# P-MT3620RDB-1-7_PIO.net
KiCad netlist of a schematic drawn in Altium Designer
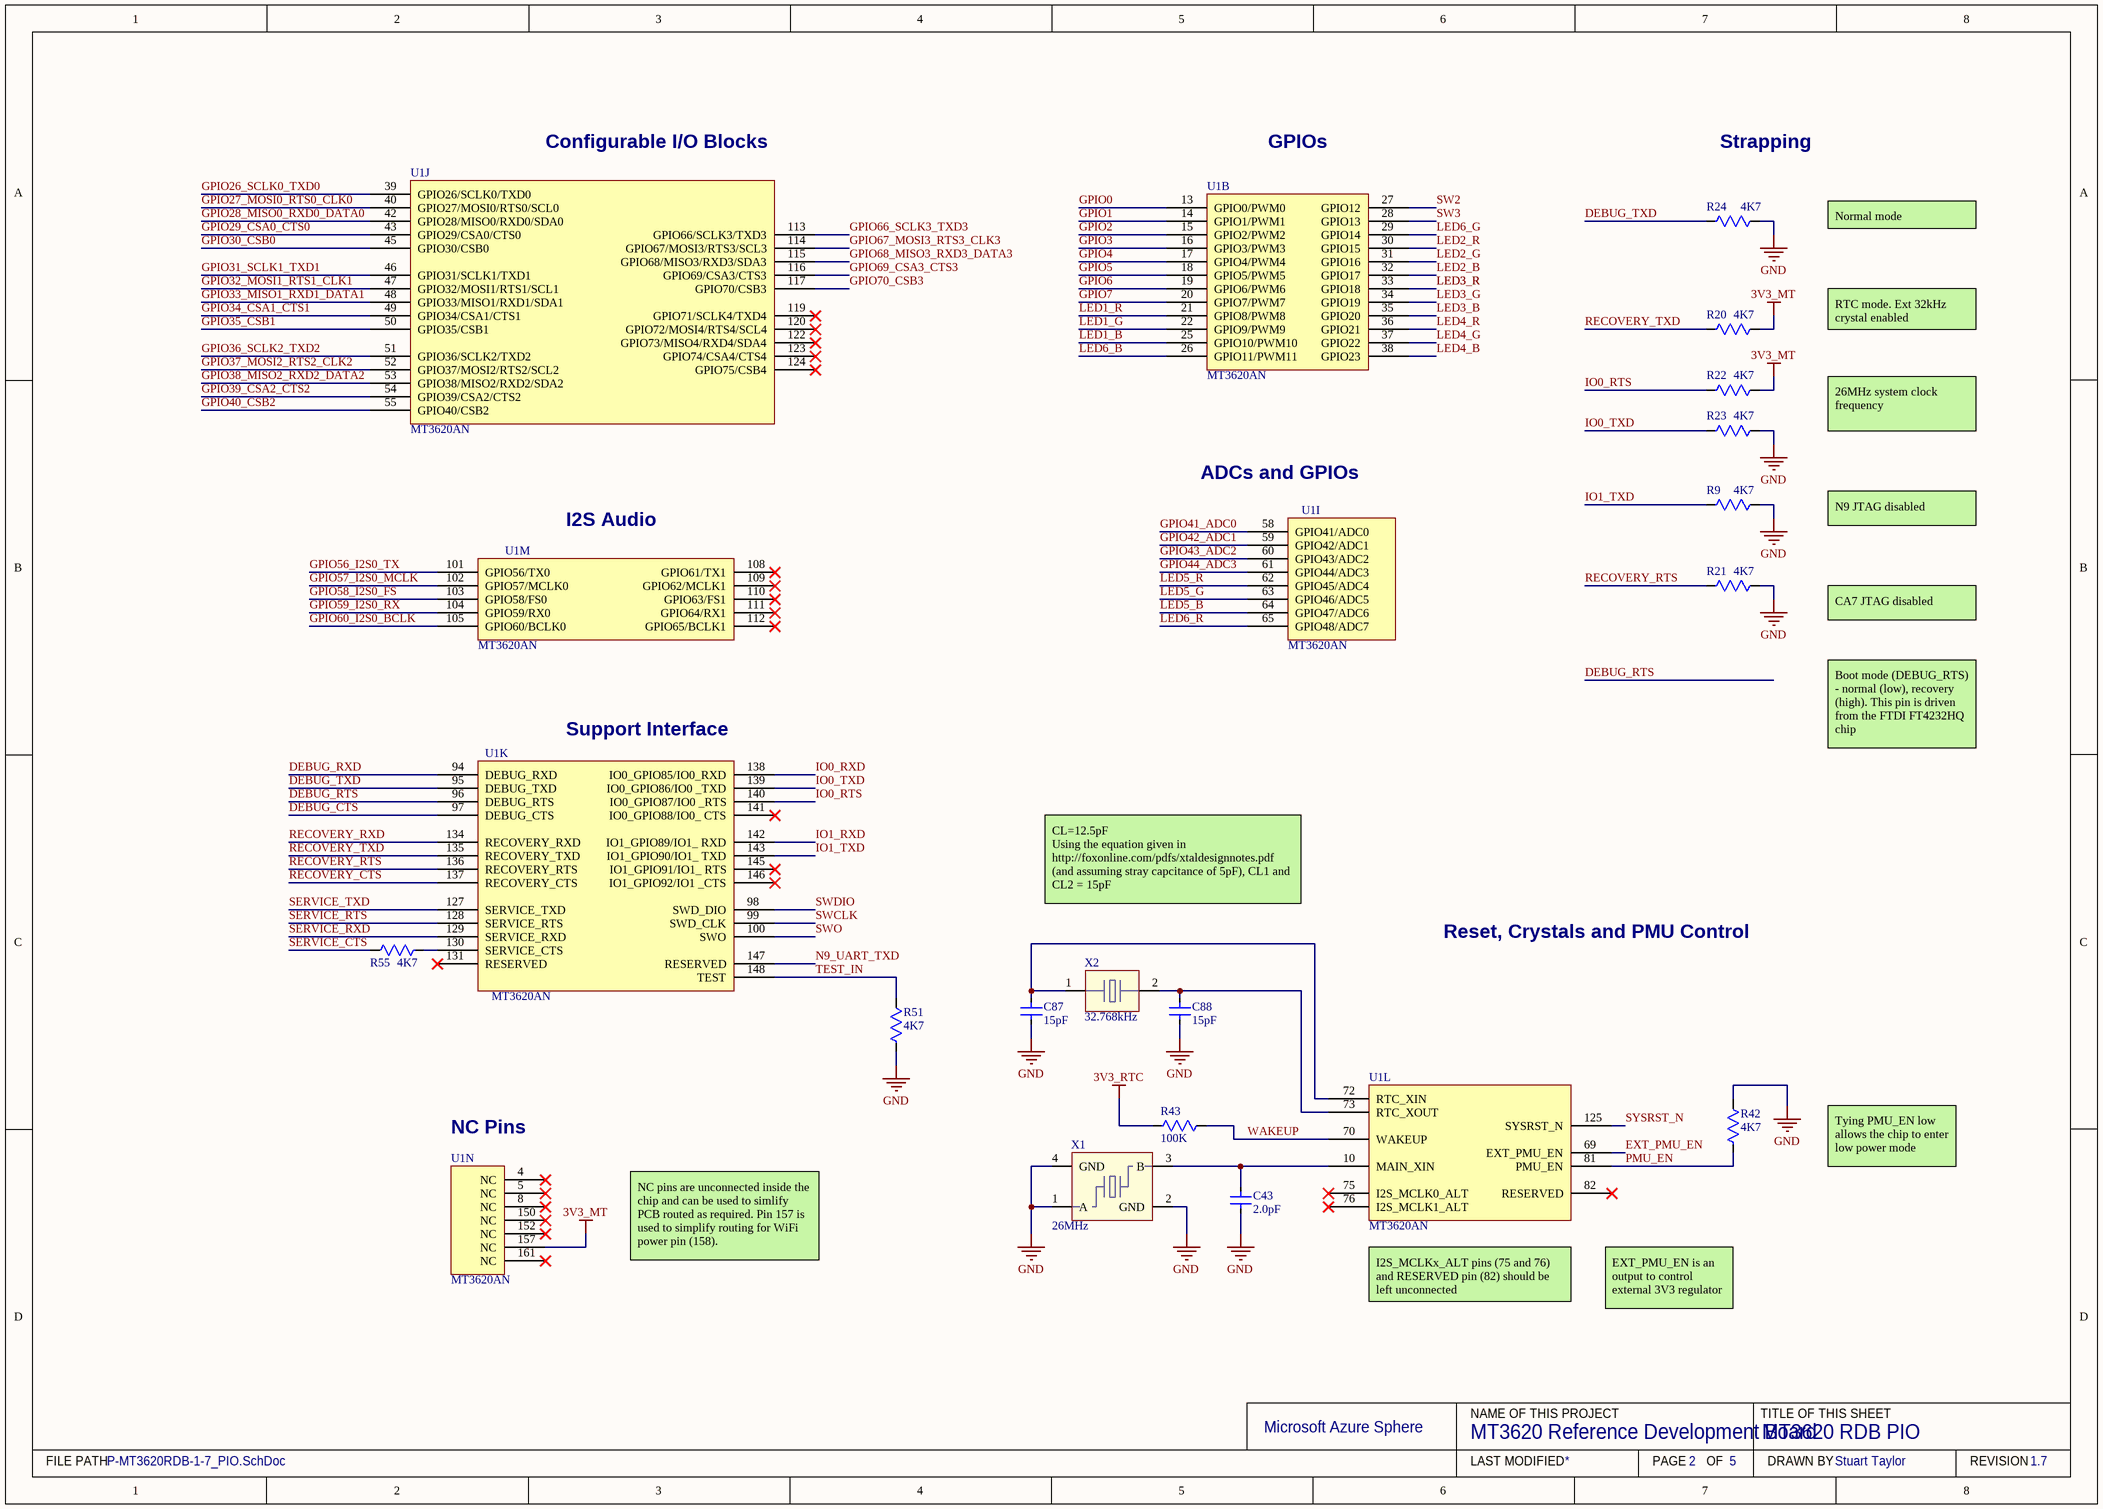
[diagram p0: P-MT3620RDB-1-7_PIO.SchDoc]

(export (version "E")
  (design (tool "Eeschema 10.0.6"))
  (components
    (comp (ref "C43")
      (value "2.0pF")
      (footprint "CAPC1005-EIA0402 0.55MM MED")
      (description "CAP CER 2PF 50V NP0 0402")
      (fields
        (field (name "MANUFACTURER") "TDK Corporation")
        (field (name "MANUFACTURER PART NUMBER") "C1005C0G1H020C050BA")
        (field (name "CAPACITANCE") "2.0pF")
      )
      (libsource (lib "TDK_Capacitor_C_0402") (part "2.0pF 0402 C0G, NP0 50V"))
    )
    (comp (ref "C87")
      (value "15pF")
      (footprint "CAPC1005-EIA0402 0.55MM MED")
      (description "CAP CER 15PF 50V 5% NP0 0402")
      (fields
        (field (name "MANUFACTURER") "TDK Corporation")
        (field (name "MANUFACTURER PART NUMBER") "C1005C0G1H150J050BA")
        (field (name "CAPACITANCE") "15pF")
      )
      (libsource (lib "TDK_Capacitor_C_0402") (part "15pF 0402 C0G, NP0 50V"))
    )
    (comp (ref "C88")
      (value "15pF")
      (footprint "CAPC1005-EIA0402 0.55MM MED")
      (description "CAP CER 15PF 50V 5% NP0 0402")
      (fields
        (field (name "MANUFACTURER") "TDK Corporation")
        (field (name "MANUFACTURER PART NUMBER") "C1005C0G1H150J050BA")
        (field (name "CAPACITANCE") "15pF")
      )
      (libsource (lib "TDK_Capacitor_C_0402") (part "15pF 0402 C0G, NP0 50V"))
    )
    (comp (ref "R9")
      (value "4K7")
      (footprint "RES 0402 MEDIUM DENSITY")
      (description "RES 4.7K OHM 1/10W 1% 0402 SMD")
      (fields
        (field (name "MANUFACTURER") "Panasonic Electronic Components")
        (field (name "MANUFACTURER PART NUMBER") "ERJ-2RKF4701X")
        (field (name "RESISTANCE (OHMS)") "4K7")
      )
      (libsource (lib "Panasonic_Resistor_ERJ2R") (part "4.7K"))
    )
    (comp (ref "R20")
      (value "4K7")
      (footprint "RES 0402 MEDIUM DENSITY")
      (description "RES 4.7K OHM 1/10W 1% 0402 SMD")
      (fields
        (field (name "MANUFACTURER") "Panasonic Electronic Components")
        (field (name "MANUFACTURER PART NUMBER") "ERJ-2RKF4701X")
        (field (name "RESISTANCE (OHMS)") "4K7")
      )
      (libsource (lib "Panasonic_Resistor_ERJ2R") (part "4.7K"))
    )
    (comp (ref "R21")
      (value "4K7")
      (footprint "RES 0402 MEDIUM DENSITY")
      (description "RES 4.7K OHM 1/10W 1% 0402 SMD")
      (fields
        (field (name "MANUFACTURER") "Panasonic Electronic Components")
        (field (name "MANUFACTURER PART NUMBER") "ERJ-2RKF4701X")
        (field (name "RESISTANCE (OHMS)") "4K7")
      )
      (libsource (lib "Panasonic_Resistor_ERJ2R") (part "4.7K"))
    )
    (comp (ref "R22")
      (value "4K7")
      (footprint "RES 0402 MEDIUM DENSITY")
      (description "RES 4.7K OHM 1/10W 1% 0402 SMD")
      (fields
        (field (name "MANUFACTURER") "Panasonic Electronic Components")
        (field (name "MANUFACTURER PART NUMBER") "ERJ-2RKF4701X")
        (field (name "RESISTANCE (OHMS)") "4K7")
      )
      (libsource (lib "Panasonic_Resistor_ERJ2R") (part "4.7K"))
    )
    (comp (ref "R23")
      (value "4K7")
      (footprint "RES 0402 MEDIUM DENSITY")
      (description "RES 4.7K OHM 1/10W 1% 0402 SMD")
      (fields
        (field (name "MANUFACTURER") "Panasonic Electronic Components")
        (field (name "MANUFACTURER PART NUMBER") "ERJ-2RKF4701X")
        (field (name "RESISTANCE (OHMS)") "4K7")
      )
      (libsource (lib "Panasonic_Resistor_ERJ2R") (part "4.7K"))
    )
    (comp (ref "R24")
      (value "4K7")
      (footprint "RES 0402 MEDIUM DENSITY")
      (description "RES 4.7K OHM 1/10W 1% 0402 SMD")
      (fields
        (field (name "MANUFACTURER") "Panasonic Electronic Components")
        (field (name "MANUFACTURER PART NUMBER") "ERJ-2RKF4701X")
        (field (name "RESISTANCE (OHMS)") "4K7")
      )
      (libsource (lib "Panasonic_Resistor_ERJ2R") (part "4.7K"))
    )
    (comp (ref "R42")
      (value "4K7")
      (footprint "RES 0402 MEDIUM DENSITY")
      (description "RES 4.7K OHM 1/10W 1% 0402 SMD")
      (fields
        (field (name "MANUFACTURER") "Panasonic Electronic Components")
        (field (name "MANUFACTURER PART NUMBER") "ERJ-2RKF4701X")
        (field (name "RESISTANCE (OHMS)") "4K7")
      )
      (libsource (lib "Panasonic_Resistor_ERJ2R") (part "4.7K"))
    )
    (comp (ref "R43")
      (value "100K")
      (footprint "RES 0402 MEDIUM DENSITY")
      (description "RES 100K OHM 1/10W 1% 0402 SMD")
      (fields
        (field (name "MANUFACTURER") "Panasonic Electronic Components")
        (field (name "MANUFACTURER PART NUMBER") "ERJ-2RKF1003X")
        (field (name "RESISTANCE (OHMS)") "100K")
      )
      (libsource (lib "Panasonic_Resistor_ERJ2R") (part "100K"))
    )
    (comp (ref "R51")
      (value "4K7")
      (footprint "RES 0402 MEDIUM DENSITY")
      (description "RES 4.7K OHM 1/10W 1% 0402 SMD")
      (fields
        (field (name "MANUFACTURER") "Panasonic Electronic Components")
        (field (name "MANUFACTURER PART NUMBER") "ERJ-2RKF4701X")
        (field (name "RESISTANCE (OHMS)") "4K7")
      )
      (libsource (lib "Panasonic_Resistor_ERJ2R") (part "4.7K"))
    )
    (comp (ref "R55")
      (value "4K7")
      (footprint "RES 0402 MEDIUM DENSITY")
      (description "RES 4.7K OHM 1/10W 1% 0402 SMD")
      (fields
        (field (name "MANUFACTURER") "Panasonic Electronic Components")
        (field (name "MANUFACTURER PART NUMBER") "ERJ-2RKF4701X")
        (field (name "RESISTANCE (OHMS)") "4K7")
      )
      (libsource (lib "Panasonic_Resistor_ERJ2R") (part "4.7K"))
    )
    (comp (ref "U1")
      (value "MT3620AN")
      (footprint "MT3620_MaskSquaresVias50")
      (fields (field (name "MANUFACTURER") "MediaTek Inc."))
      (libsource (lib "Microsoft") (part "MT3620AN"))
    )
    (comp (ref "X1")
      (value "26MHz")
      (footprint "CT2520DB26000C0FZZA1")
      (description "26MHz crystal")
      (fields
        (field (name "MANUFACTURER") "Siward")
        (field (name "MANUFACTURER PART NUMBER") "XTL581100-M118-0804")
      )
      (libsource (lib "Siward") (part "XTL581100-M118-0804"))
    )
    (comp (ref "X2")
      (value "32.768kHz")
      (footprint "9HT10-32.768KDZF-T")
      (description "32.768kHz ±20ppm Crystal 12.5pF 70 kOhm -40°C ~ 85°C  Surface Mount 2-SMD")
      (fields
        (field (name "MANUFACTURER") "TXC")
        (field (name "MANUFACTURER PART NUMBER") "9HT10-32.768KDZF-T")
      )
      (libsource (lib "TXC") (part "9HT10-32.768KDZF-T"))
    )
  )
  (nets
    (net (code "1") (name "/DEBUG_CTS") (class "Default")
      (node (ref "U1") (pin "97") (pinfunction "DEBUG_CTS_97") (pintype "passive"))
    )
    (net (code "2") (name "/DEBUG_RTS") (class "Default")
      (node (ref "U1") (pin "96") (pinfunction "DEBUG_RTS_96") (pintype "passive"))
    )
    (net (code "3") (name "/DEBUG_RXD") (class "Default")
      (node (ref "U1") (pin "94") (pinfunction "DEBUG_RXD_94") (pintype "passive"))
    )
    (net (code "4") (name "/DEBUG_TXD") (class "Default")
      (node (ref "R24") (pin "2") (pinfunction "2_2") (pintype "passive"))
      (node (ref "U1") (pin "95") (pinfunction "DEBUG_TXD_95") (pintype "passive"))
    )
    (net (code "5") (name "/EXT_PMU_EN") (class "Default")
      (node (ref "U1") (pin "69") (pinfunction "EXT_PMU_EN_69") (pintype "passive"))
    )
    (net (code "6") (name "/GPIO0") (class "Default")
      (node (ref "U1") (pin "13") (pinfunction "GPIO0/PWM0_13") (pintype "passive"))
    )
    (net (code "7") (name "/GPIO1") (class "Default")
      (node (ref "U1") (pin "14") (pinfunction "GPIO1/PWM1_14") (pintype "passive"))
    )
    (net (code "8") (name "/GPIO2") (class "Default")
      (node (ref "U1") (pin "15") (pinfunction "GPIO2/PWM2_15") (pintype "passive"))
    )
    (net (code "9") (name "/GPIO3") (class "Default")
      (node (ref "U1") (pin "16") (pinfunction "GPIO3/PWM3_16") (pintype "passive"))
    )
    (net (code "10") (name "/GPIO4") (class "Default")
      (node (ref "U1") (pin "17") (pinfunction "GPIO4/PWM4_17") (pintype "passive"))
    )
    (net (code "11") (name "/GPIO5") (class "Default")
      (node (ref "U1") (pin "18") (pinfunction "GPIO5/PWM5_18") (pintype "passive"))
    )
    (net (code "12") (name "/GPIO6") (class "Default")
      (node (ref "U1") (pin "19") (pinfunction "GPIO6/PWM6_19") (pintype "passive"))
    )
    (net (code "13") (name "/GPIO7") (class "Default")
      (node (ref "U1") (pin "20") (pinfunction "GPIO7/PWM7_20") (pintype "passive"))
    )
    (net (code "14") (name "/GPIO26_SCLK0_TXD0") (class "Default")
      (node (ref "U1") (pin "39") (pinfunction "GPIO26/SCLK0/TXD0_39") (pintype "passive"))
    )
    (net (code "15") (name "/GPIO27_MOSI0_RTS0_CLK0") (class "Default")
      (node (ref "U1") (pin "40") (pinfunction "GPIO27/MOSI0/RTS0/SCL0_40") (pintype "passive"))
    )
    (net (code "16") (name "/GPIO28_MISO0_RXD0_DATA0") (class "Default")
      (node (ref "U1") (pin "42") (pinfunction "GPIO28/MISO0/RXD0/SDA0_42") (pintype "passive"))
    )
    (net (code "17") (name "/GPIO29_CSA0_CTS0") (class "Default")
      (node (ref "U1") (pin "43") (pinfunction "GPIO29/CSA0/CTS0_43") (pintype "passive"))
    )
    (net (code "18") (name "/GPIO30_CSB0") (class "Default")
      (node (ref "U1") (pin "45") (pinfunction "GPIO30/CSB0_45") (pintype "passive"))
    )
    (net (code "19") (name "/GPIO31_SCLK1_TXD1") (class "Default")
      (node (ref "U1") (pin "46") (pinfunction "GPIO31/SCLK1/TXD1_46") (pintype "passive"))
    )
    (net (code "20") (name "/GPIO32_MOSI1_RTS1_CLK1") (class "Default")
      (node (ref "U1") (pin "47") (pinfunction "GPIO32/MOSI1/RTS1/SCL1_47") (pintype "passive"))
    )
    (net (code "21") (name "/GPIO33_MISO1_RXD1_DATA1") (class "Default")
      (node (ref "U1") (pin "48") (pinfunction "GPIO33/MISO1/RXD1/SDA1_48") (pintype "passive"))
    )
    (net (code "22") (name "/GPIO34_CSA1_CTS1") (class "Default")
      (node (ref "U1") (pin "49") (pinfunction "GPIO34/CSA1/CTS1_49") (pintype "passive"))
    )
    (net (code "23") (name "/GPIO35_CSB1") (class "Default")
      (node (ref "U1") (pin "50") (pinfunction "GPIO35/CSB1_50") (pintype "passive"))
    )
    (net (code "24") (name "/GPIO36_SCLK2_TXD2") (class "Default")
      (node (ref "U1") (pin "51") (pinfunction "GPIO36/SCLK2/TXD2_51") (pintype "passive"))
    )
    (net (code "25") (name "/GPIO37_MOSI2_RTS2_CLK2") (class "Default")
      (node (ref "U1") (pin "52") (pinfunction "GPIO37/MOSI2/RTS2/SCL2_52") (pintype "passive"))
    )
    (net (code "26") (name "/GPIO38_MISO2_RXD2_DATA2") (class "Default")
      (node (ref "U1") (pin "53") (pinfunction "GPIO38/MISO2/RXD2/SDA2_53") (pintype "passive"))
    )
    (net (code "27") (name "/GPIO39_CSA2_CTS2") (class "Default")
      (node (ref "U1") (pin "54") (pinfunction "GPIO39/CSA2/CTS2_54") (pintype "passive"))
    )
    (net (code "28") (name "/GPIO40_CSB2") (class "Default")
      (node (ref "U1") (pin "55") (pinfunction "GPIO40/CSB2_55") (pintype "passive"))
    )
    (net (code "29") (name "/GPIO41_ADC0") (class "Default")
      (node (ref "U1") (pin "58") (pinfunction "GPIO41/ADC0_58") (pintype "passive"))
    )
    (net (code "30") (name "/GPIO42_ADC1") (class "Default")
      (node (ref "U1") (pin "59") (pinfunction "GPIO42/ADC1_59") (pintype "passive"))
    )
    (net (code "31") (name "/GPIO43_ADC2") (class "Default")
      (node (ref "U1") (pin "60") (pinfunction "GPIO43/ADC2_60") (pintype "passive"))
    )
    (net (code "32") (name "/GPIO44_ADC3") (class "Default")
      (node (ref "U1") (pin "61") (pinfunction "GPIO44/ADC3_61") (pintype "passive"))
    )
    (net (code "33") (name "/GPIO56_I2S0_TX") (class "Default")
      (node (ref "U1") (pin "101") (pinfunction "GPIO56/TX0_101") (pintype "passive"))
    )
    (net (code "34") (name "/GPIO57_I2S0_MCLK") (class "Default")
      (node (ref "U1") (pin "102") (pinfunction "GPIO57/MCLK0_102") (pintype "passive"))
    )
    (net (code "35") (name "/GPIO58_I2S0_FS") (class "Default")
      (node (ref "U1") (pin "103") (pinfunction "GPIO58/FS0_103") (pintype "passive"))
    )
    (net (code "36") (name "/GPIO59_I2S0_RX") (class "Default")
      (node (ref "U1") (pin "104") (pinfunction "GPIO59/RX0_104") (pintype "passive"))
    )
    (net (code "37") (name "/GPIO60_I2S0_BCLK") (class "Default")
      (node (ref "U1") (pin "105") (pinfunction "GPIO60/BCLK0_105") (pintype "passive"))
    )
    (net (code "38") (name "/GPIO66_SCLK3_TXD3") (class "Default")
      (node (ref "U1") (pin "113") (pinfunction "GPIO66/SCLK3/TXD3_113") (pintype "passive"))
    )
    (net (code "39") (name "/GPIO67_MOSI3_RTS3_CLK3") (class "Default")
      (node (ref "U1") (pin "114") (pinfunction "GPIO67/MOSI3/RTS3/SCL3_114") (pintype "passive"))
    )
    (net (code "40") (name "/GPIO68_MISO3_RXD3_DATA3") (class "Default")
      (node (ref "U1") (pin "115") (pinfunction "GPIO68/MISO3/RXD3/SDA3_115") (pintype "passive"))
    )
    (net (code "41") (name "/GPIO69_CSA3_CTS3") (class "Default")
      (node (ref "U1") (pin "116") (pinfunction "GPIO69/CSA3/CTS3_116") (pintype "passive"))
    )
    (net (code "42") (name "/GPIO70_CSB3") (class "Default")
      (node (ref "U1") (pin "117") (pinfunction "GPIO70/CSB3_117") (pintype "passive"))
    )
    (net (code "43") (name "/IO0_RTS") (class "Default")
      (node (ref "R22") (pin "2") (pinfunction "2_2") (pintype "passive"))
      (node (ref "U1") (pin "140") (pinfunction "IO0_GPIO87/IO0__RTS_140") (pintype "passive"))
    )
    (net (code "44") (name "/IO0_RXD") (class "Default")
      (node (ref "U1") (pin "138") (pinfunction "IO0_GPIO85/IO0_RXD_138") (pintype "passive"))
    )
    (net (code "45") (name "/IO0_TXD") (class "Default")
      (node (ref "R23") (pin "2") (pinfunction "2_2") (pintype "passive"))
      (node (ref "U1") (pin "139") (pinfunction "IO0_GPIO86/IO0__TXD_139") (pintype "passive"))
    )
    (net (code "46") (name "/IO1_RXD") (class "Default")
      (node (ref "U1") (pin "142") (pinfunction "IO1_GPIO89/IO1__RXD_142") (pintype "passive"))
    )
    (net (code "47") (name "/IO1_TXD") (class "Default")
      (node (ref "R9") (pin "2") (pinfunction "2_2") (pintype "passive"))
      (node (ref "U1") (pin "143") (pinfunction "IO1_GPIO90/IO1__TXD_143") (pintype "passive"))
    )
    (net (code "48") (name "/LED1_B") (class "Default")
      (node (ref "U1") (pin "25") (pinfunction "GPIO10/PWM10_25") (pintype "passive"))
    )
    (net (code "49") (name "/LED1_G") (class "Default")
      (node (ref "U1") (pin "22") (pinfunction "GPIO9/PWM9_22") (pintype "passive"))
    )
    (net (code "50") (name "/LED1_R") (class "Default")
      (node (ref "U1") (pin "21") (pinfunction "GPIO8/PWM8_21") (pintype "passive"))
    )
    (net (code "51") (name "/LED2_B") (class "Default")
      (node (ref "U1") (pin "32") (pinfunction "GPIO17_32") (pintype "passive"))
    )
    (net (code "52") (name "/LED2_G") (class "Default")
      (node (ref "U1") (pin "31") (pinfunction "GPIO16_31") (pintype "passive"))
    )
    (net (code "53") (name "/LED2_R") (class "Default")
      (node (ref "U1") (pin "30") (pinfunction "GPIO15_30") (pintype "passive"))
    )
    (net (code "54") (name "/LED3_B") (class "Default")
      (node (ref "U1") (pin "35") (pinfunction "GPIO20_35") (pintype "passive"))
    )
    (net (code "55") (name "/LED3_G") (class "Default")
      (node (ref "U1") (pin "34") (pinfunction "GPIO19_34") (pintype "passive"))
    )
    (net (code "56") (name "/LED3_R") (class "Default")
      (node (ref "U1") (pin "33") (pinfunction "GPIO18_33") (pintype "passive"))
    )
    (net (code "57") (name "/LED4_B") (class "Default")
      (node (ref "U1") (pin "38") (pinfunction "GPIO23_38") (pintype "passive"))
    )
    (net (code "58") (name "/LED4_G") (class "Default")
      (node (ref "U1") (pin "37") (pinfunction "GPIO22_37") (pintype "passive"))
    )
    (net (code "59") (name "/LED4_R") (class "Default")
      (node (ref "U1") (pin "36") (pinfunction "GPIO21_36") (pintype "passive"))
    )
    (net (code "60") (name "/LED5_B") (class "Default")
      (node (ref "U1") (pin "64") (pinfunction "GPIO47/ADC6_64") (pintype "passive"))
    )
    (net (code "61") (name "/LED5_G") (class "Default")
      (node (ref "U1") (pin "63") (pinfunction "GPIO46/ADC5_63") (pintype "passive"))
    )
    (net (code "62") (name "/LED5_R") (class "Default")
      (node (ref "U1") (pin "62") (pinfunction "GPIO45/ADC4_62") (pintype "passive"))
    )
    (net (code "63") (name "/LED6_B") (class "Default")
      (node (ref "U1") (pin "26") (pinfunction "GPIO11/PWM11_26") (pintype "passive"))
    )
    (net (code "64") (name "/LED6_G") (class "Default")
      (node (ref "U1") (pin "29") (pinfunction "GPIO14_29") (pintype "passive"))
    )
    (net (code "65") (name "/LED6_R") (class "Default")
      (node (ref "U1") (pin "65") (pinfunction "GPIO48/ADC7_65") (pintype "passive"))
    )
    (net (code "66") (name "/N9_UART_TXD") (class "Default")
      (node (ref "U1") (pin "147") (pinfunction "RESERVED_147") (pintype "passive"))
    )
    (net (code "67") (name "/PMU_EN") (class "Default")
      (node (ref "R42") (pin "2") (pinfunction "2_2") (pintype "passive"))
      (node (ref "U1") (pin "81") (pinfunction "PMU_EN_81") (pintype "passive"))
    )
    (net (code "68") (name "/RECOVERY_CTS") (class "Default")
      (node (ref "U1") (pin "137") (pinfunction "RECOVERY_CTS_137") (pintype "passive"))
    )
    (net (code "69") (name "/RECOVERY_RTS") (class "Default")
      (node (ref "R21") (pin "2") (pinfunction "2_2") (pintype "passive"))
      (node (ref "U1") (pin "136") (pinfunction "RECOVERY_RTS_136") (pintype "passive"))
    )
    (net (code "70") (name "/RECOVERY_RXD") (class "Default")
      (node (ref "U1") (pin "134") (pinfunction "RECOVERY_RXD_134") (pintype "passive"))
    )
    (net (code "71") (name "/RECOVERY_TXD") (class "Default")
      (node (ref "R20") (pin "2") (pinfunction "2_2") (pintype "passive"))
      (node (ref "U1") (pin "135") (pinfunction "RECOVERY_TXD_135") (pintype "passive"))
    )
    (net (code "72") (name "/SERVICE_CTS") (class "Default")
      (node (ref "R55") (pin "1") (pinfunction "1_1") (pintype "passive"))
    )
    (net (code "73") (name "/SERVICE_RTS") (class "Default")
      (node (ref "U1") (pin "128") (pinfunction "SERVICE_RTS_128") (pintype "passive"))
    )
    (net (code "74") (name "/SERVICE_RXD") (class "Default")
      (node (ref "U1") (pin "129") (pinfunction "SERVICE_RXD_129") (pintype "passive"))
    )
    (net (code "75") (name "/SERVICE_TXD") (class "Default")
      (node (ref "U1") (pin "127") (pinfunction "SERVICE_TXD_127") (pintype "passive"))
    )
    (net (code "76") (name "/SW2") (class "Default")
      (node (ref "U1") (pin "27") (pinfunction "GPIO12_27") (pintype "passive"))
    )
    (net (code "77") (name "/SW3") (class "Default")
      (node (ref "U1") (pin "28") (pinfunction "GPIO13_28") (pintype "passive"))
    )
    (net (code "78") (name "/SWCLK") (class "Default")
      (node (ref "U1") (pin "99") (pinfunction "SWD_CLK_99") (pintype "passive"))
    )
    (net (code "79") (name "/SWDIO") (class "Default")
      (node (ref "U1") (pin "98") (pinfunction "SWD_DIO_98") (pintype "passive"))
    )
    (net (code "80") (name "/SWO") (class "Default")
      (node (ref "U1") (pin "100") (pinfunction "SWO_100") (pintype "passive"))
    )
    (net (code "81") (name "/SYSRST_N") (class "Default")
      (node (ref "U1") (pin "125") (pinfunction "SYSRST_N_125") (pintype "passive"))
    )
    (net (code "82") (name "/TEST_IN") (class "Default")
      (node (ref "R51") (pin "1") (pinfunction "1_1") (pintype "passive"))
      (node (ref "U1") (pin "148") (pinfunction "TEST_148") (pintype "passive"))
    )
    (net (code "83") (name "/WAKEUP") (class "Default")
      (node (ref "R43") (pin "1") (pinfunction "1_1") (pintype "passive"))
      (node (ref "U1") (pin "70") (pinfunction "WAKEUP_70") (pintype "passive"))
    )
    (net (code "84") (name "3V3_MT") (class "Default")
      (node (ref "R20") (pin "1") (pinfunction "1_1") (pintype "passive"))
      (node (ref "R22") (pin "1") (pinfunction "1_1") (pintype "passive"))
      (node (ref "U1") (pin "157") (pinfunction "NC_157") (pintype "passive"))
    )
    (net (code "85") (name "3V3_RTC") (class "Default")
      (node (ref "R43") (pin "2") (pinfunction "2_2") (pintype "passive"))
    )
    (net (code "86") (name "GND") (class "Default")
      (node (ref "C43") (pin "1") (pinfunction "1_1") (pintype "passive"))
      (node (ref "C87") (pin "1") (pinfunction "1_1") (pintype "passive"))
      (node (ref "C88") (pin "1") (pinfunction "1_1") (pintype "passive"))
      (node (ref "R21") (pin "1") (pinfunction "1_1") (pintype "passive"))
      (node (ref "R23") (pin "1") (pinfunction "1_1") (pintype "passive"))
      (node (ref "R24") (pin "1") (pinfunction "1_1") (pintype "passive"))
      (node (ref "R42") (pin "1") (pinfunction "1_1") (pintype "passive"))
      (node (ref "R51") (pin "2") (pinfunction "2_2") (pintype "passive"))
      (node (ref "R9") (pin "1") (pinfunction "1_1") (pintype "passive"))
      (node (ref "X1") (pin "1") (pinfunction "A_1") (pintype "passive"))
      (node (ref "X1") (pin "2") (pinfunction "GND_2") (pintype "passive"))
      (node (ref "X1") (pin "4") (pinfunction "GND_4") (pintype "passive"))
    )
    (net (code "87") (name "Net-(U1K-SERVICE_CTS)") (class "Default")
      (node (ref "R55") (pin "2") (pinfunction "2_2") (pintype "passive"))
      (node (ref "U1") (pin "130") (pinfunction "SERVICE_CTS_130") (pintype "passive"))
    )
    (net (code "88") (name "Net-(U1L-MAIN_XIN)") (class "Default")
      (node (ref "C43") (pin "2") (pinfunction "2_2") (pintype "passive"))
      (node (ref "U1") (pin "10") (pinfunction "MAIN_XIN_10") (pintype "passive"))
      (node (ref "X1") (pin "3") (pinfunction "B_3") (pintype "passive"))
    )
    (net (code "89") (name "Net-(U1L-RTC_XIN)") (class "Default")
      (node (ref "C87") (pin "2") (pinfunction "2_2") (pintype "passive"))
      (node (ref "U1") (pin "72") (pinfunction "RTC_XIN_72") (pintype "passive"))
      (node (ref "X2") (pin "1") (pinfunction "1_1") (pintype "passive"))
    )
    (net (code "90") (name "Net-(U1L-RTC_XOUT)") (class "Default")
      (node (ref "C88") (pin "2") (pinfunction "2_2") (pintype "passive"))
      (node (ref "U1") (pin "73") (pinfunction "RTC_XOUT_73") (pintype "passive"))
      (node (ref "X2") (pin "2") (pinfunction "2_2") (pintype "passive"))
    )
    (net (code "91") (name "unconnected-(U1J-GPIO71{slash}SCLK4{slash}TXD4-Pad119)") (class "Default")
      (node (ref "U1") (pin "119") (pinfunction "GPIO71/SCLK4/TXD4_119") (pintype "passive+no_connect"))
    )
    (net (code "92") (name "unconnected-(U1J-GPIO72{slash}MOSI4{slash}RTS4{slash}SCL4-Pad120)") (class "Default")
      (node (ref "U1") (pin "120") (pinfunction "GPIO72/MOSI4/RTS4/SCL4_120") (pintype "passive+no_connect"))
    )
    (net (code "93") (name "unconnected-(U1J-GPIO73{slash}MISO4{slash}RXD4{slash}SDA4-Pad122)") (class "Default")
      (node (ref "U1") (pin "122") (pinfunction "GPIO73/MISO4/RXD4/SDA4_122") (pintype "passive+no_connect"))
    )
    (net (code "94") (name "unconnected-(U1J-GPIO74{slash}CSA4{slash}CTS4-Pad123)") (class "Default")
      (node (ref "U1") (pin "123") (pinfunction "GPIO74/CSA4/CTS4_123") (pintype "passive+no_connect"))
    )
    (net (code "95") (name "unconnected-(U1J-GPIO75{slash}CSB4-Pad124)") (class "Default")
      (node (ref "U1") (pin "124") (pinfunction "GPIO75/CSB4_124") (pintype "passive+no_connect"))
    )
    (net (code "96") (name "unconnected-(U1K-IO0_GPIO88{slash}IO0__CTS-Pad141)") (class "Default")
      (node (ref "U1") (pin "141") (pinfunction "IO0_GPIO88/IO0__CTS_141") (pintype "passive+no_connect"))
    )
    (net (code "97") (name "unconnected-(U1K-IO1_GPIO91{slash}IO1__RTS-Pad145)") (class "Default")
      (node (ref "U1") (pin "145") (pinfunction "IO1_GPIO91/IO1__RTS_145") (pintype "passive+no_connect"))
    )
    (net (code "98") (name "unconnected-(U1K-IO1_GPIO92{slash}IO1__CTS-Pad146)") (class "Default")
      (node (ref "U1") (pin "146") (pinfunction "IO1_GPIO92/IO1__CTS_146") (pintype "passive+no_connect"))
    )
    (net (code "99") (name "unconnected-(U1K-RESERVED-Pad131)") (class "Default")
      (node (ref "U1") (pin "131") (pinfunction "RESERVED_131") (pintype "passive+no_connect"))
    )
    (net (code "100") (name "unconnected-(U1L-I2S_MCLK0_ALT-Pad75)") (class "Default")
      (node (ref "U1") (pin "75") (pinfunction "I2S_MCLK0_ALT_75") (pintype "passive+no_connect"))
    )
    (net (code "101") (name "unconnected-(U1L-I2S_MCLK1_ALT-Pad76)") (class "Default")
      (node (ref "U1") (pin "76") (pinfunction "I2S_MCLK1_ALT_76") (pintype "passive+no_connect"))
    )
    (net (code "102") (name "unconnected-(U1L-RESERVED-Pad82)") (class "Default")
      (node (ref "U1") (pin "82") (pinfunction "RESERVED_82") (pintype "passive+no_connect"))
    )
    (net (code "103") (name "unconnected-(U1M-GPIO61{slash}TX1-Pad108)") (class "Default")
      (node (ref "U1") (pin "108") (pinfunction "GPIO61/TX1_108") (pintype "passive+no_connect"))
    )
    (net (code "104") (name "unconnected-(U1M-GPIO62{slash}MCLK1-Pad109)") (class "Default")
      (node (ref "U1") (pin "109") (pinfunction "GPIO62/MCLK1_109") (pintype "passive+no_connect"))
    )
    (net (code "105") (name "unconnected-(U1M-GPIO63{slash}FS1-Pad110)") (class "Default")
      (node (ref "U1") (pin "110") (pinfunction "GPIO63/FS1_110") (pintype "passive+no_connect"))
    )
    (net (code "106") (name "unconnected-(U1M-GPIO64{slash}RX1-Pad111)") (class "Default")
      (node (ref "U1") (pin "111") (pinfunction "GPIO64/RX1_111") (pintype "passive+no_connect"))
    )
    (net (code "107") (name "unconnected-(U1M-GPIO65{slash}BCLK1-Pad112)") (class "Default")
      (node (ref "U1") (pin "112") (pinfunction "GPIO65/BCLK1_112") (pintype "passive+no_connect"))
    )
    (net (code "108") (name "unconnected-(U1N-NC-Pad4)") (class "Default")
      (node (ref "U1") (pin "4") (pinfunction "NC_4") (pintype "passive+no_connect"))
    )
    (net (code "109") (name "unconnected-(U1N-NC-Pad5)") (class "Default")
      (node (ref "U1") (pin "5") (pinfunction "NC_5") (pintype "passive+no_connect"))
    )
    (net (code "110") (name "unconnected-(U1N-NC-Pad8)") (class "Default")
      (node (ref "U1") (pin "8") (pinfunction "NC_8") (pintype "passive+no_connect"))
    )
    (net (code "111") (name "unconnected-(U1N-NC-Pad150)") (class "Default")
      (node (ref "U1") (pin "150") (pinfunction "NC_150") (pintype "passive+no_connect"))
    )
    (net (code "112") (name "unconnected-(U1N-NC-Pad152)") (class "Default")
      (node (ref "U1") (pin "152") (pinfunction "NC_152") (pintype "passive+no_connect"))
    )
    (net (code "113") (name "unconnected-(U1N-NC-Pad161)") (class "Default")
      (node (ref "U1") (pin "161") (pinfunction "NC_161") (pintype "passive+no_connect"))
    )
  )
)
